# NODE_DW1000_A_V2.net
KiCad netlist of a schematic drawn in Altium Designer
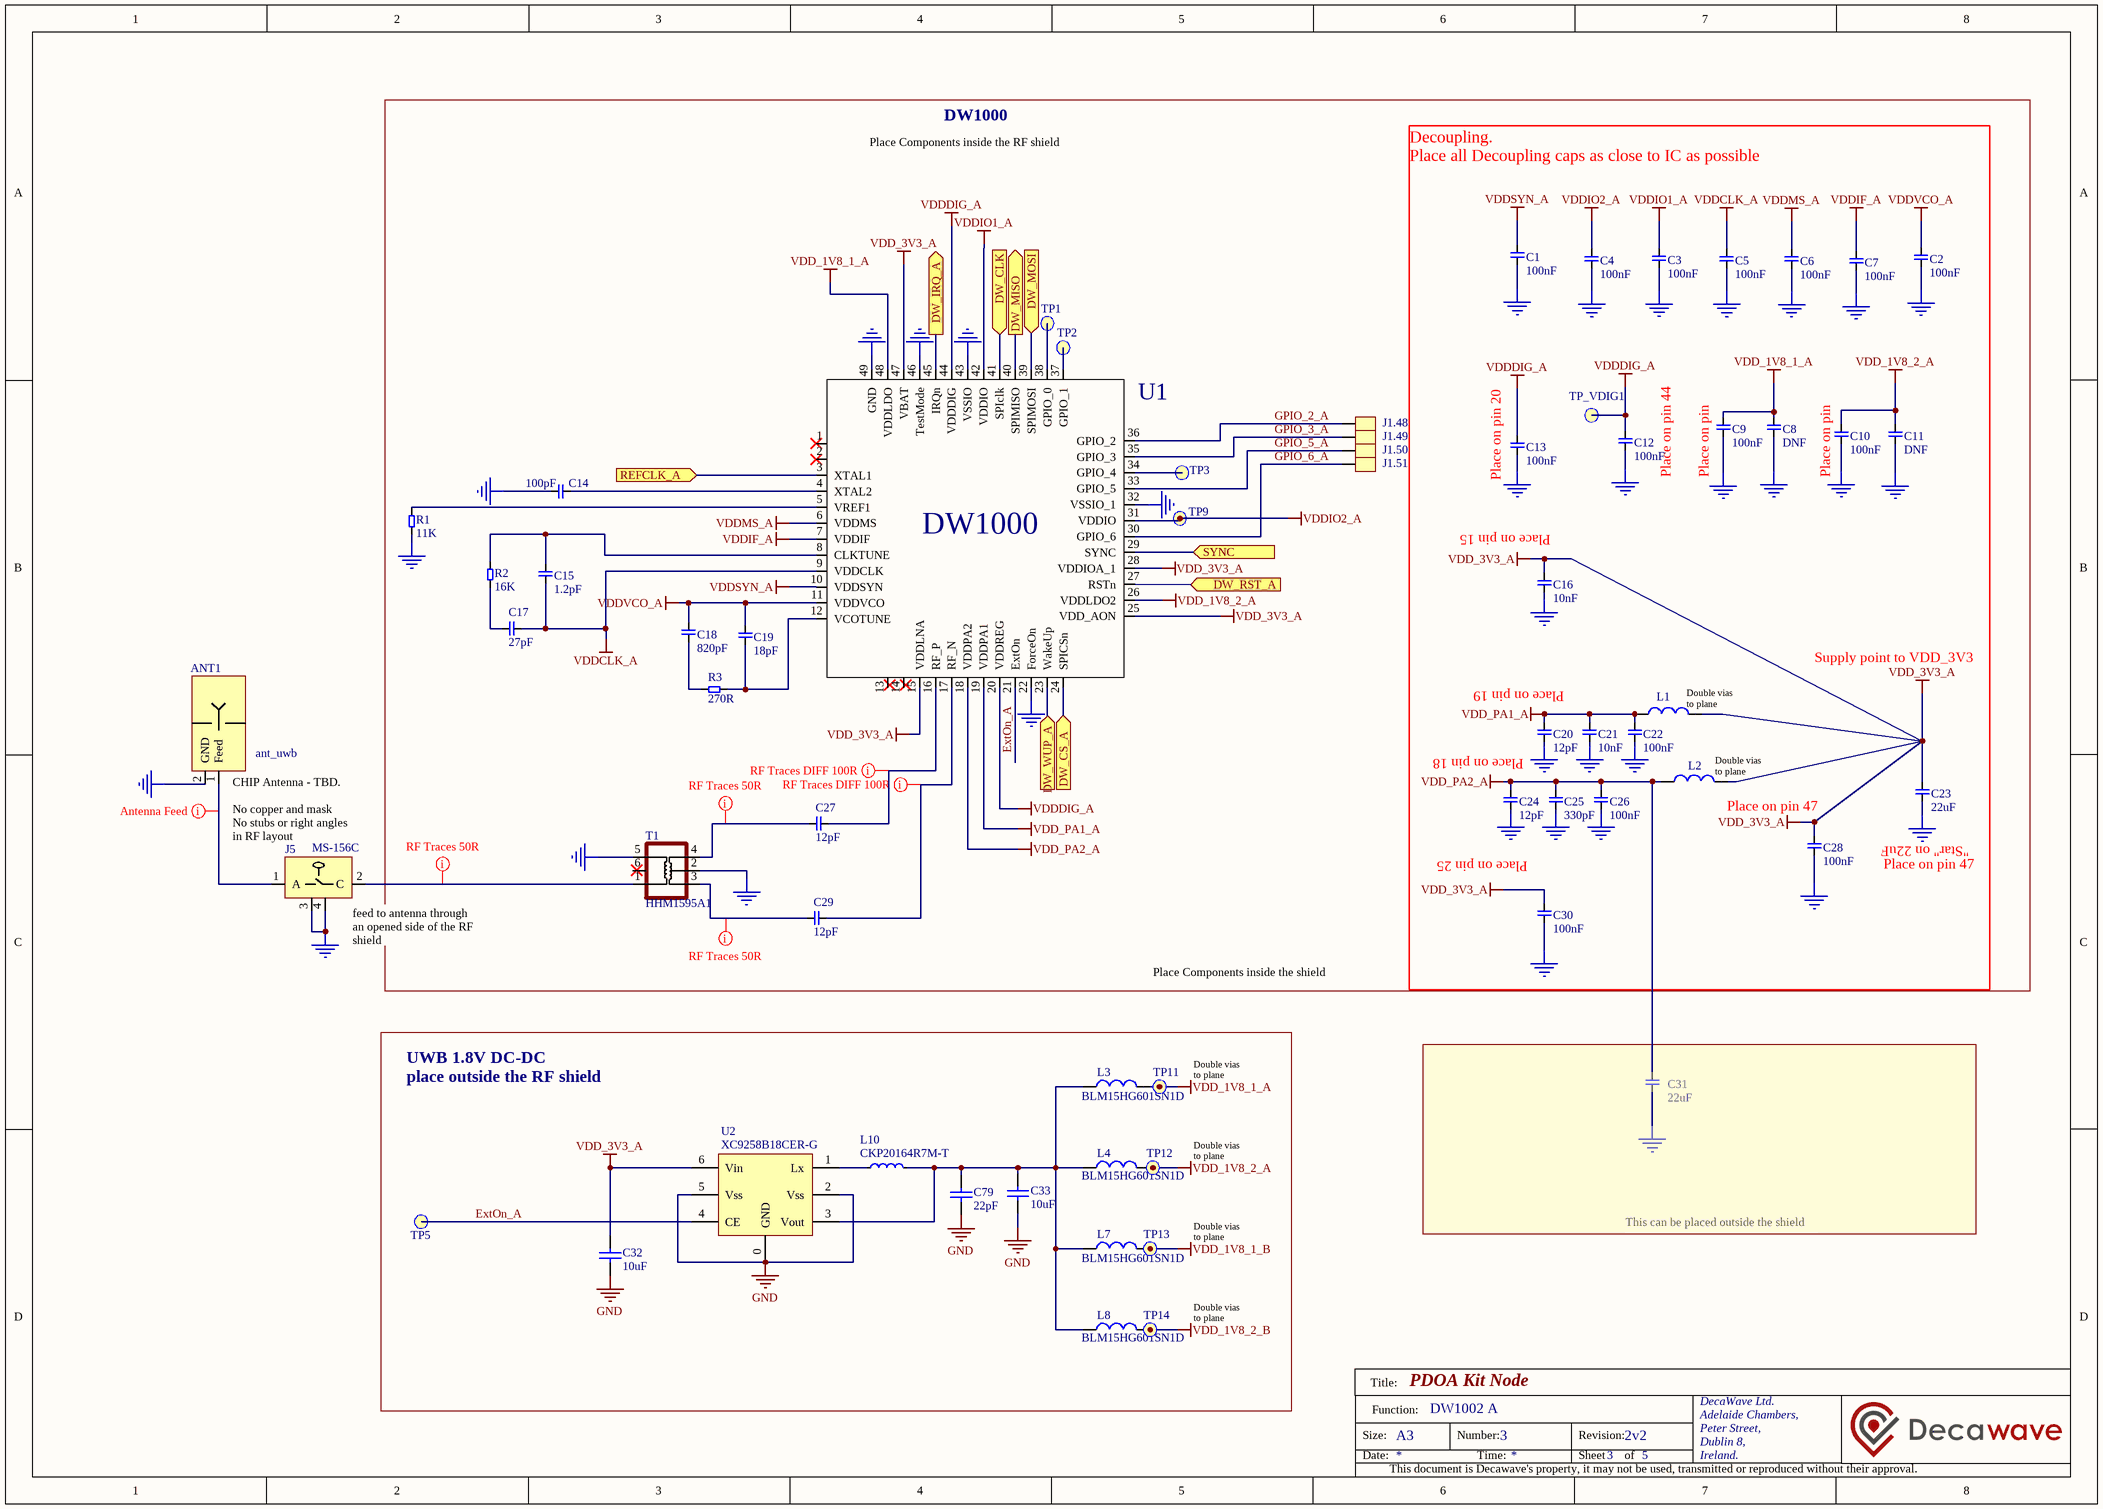
[diagram p0: NODE_DW1000_A_V2.SchDoc]

(export (version "E")
  (design (tool "Eeschema 10.0.6"))
  (components
    (comp (ref "ANT1")
      (value "ant_uwb")
      (footprint "ANT")
      (description "CHIP ANT")
      (libsource (lib "DecaWavedB") (part "ant_pcb"))
    )
    (comp (ref "C1")
      (value "100nF")
      (footprint "C0201-C")
      (description "100nF_0201_10%")
      (fields
        (field (name "MANUFACTURER") "Murata Electronics North America")
        (field (name "MANUFACTURER PART NUMBER") "GRM033C81E104KE14D")
      )
      (libsource (lib "DecaWavedB") (part "Capacitor - non polarized"))
    )
    (comp (ref "C2")
      (value "100nF")
      (footprint "C0201-C")
      (description "100nF_0201_10%")
      (fields
        (field (name "MANUFACTURER") "Murata Electronics North America")
        (field (name "MANUFACTURER PART NUMBER") "GRM033C81E104KE14D")
      )
      (libsource (lib "DecaWavedB") (part "Capacitor - non polarized"))
    )
    (comp (ref "C3")
      (value "100nF")
      (footprint "C0201-C")
      (description "100nF_0201_10%")
      (fields
        (field (name "MANUFACTURER") "Murata Electronics North America")
        (field (name "MANUFACTURER PART NUMBER") "GRM033C81E104KE14D")
      )
      (libsource (lib "DecaWavedB") (part "Capacitor - non polarized"))
    )
    (comp (ref "C4")
      (value "100nF")
      (footprint "C0201-C")
      (description "100nF_0201_10%")
      (fields
        (field (name "MANUFACTURER") "Murata Electronics North America")
        (field (name "MANUFACTURER PART NUMBER") "GRM033C81E104KE14D")
      )
      (libsource (lib "DecaWavedB") (part "Capacitor - non polarized"))
    )
    (comp (ref "C5")
      (value "100nF")
      (footprint "C0201-C")
      (description "100nF_0201_10%")
      (fields
        (field (name "MANUFACTURER") "Murata Electronics North America")
        (field (name "MANUFACTURER PART NUMBER") "GRM033C81E104KE14D")
      )
      (libsource (lib "DecaWavedB") (part "Capacitor - non polarized"))
    )
    (comp (ref "C6")
      (value "100nF")
      (footprint "C0201-C")
      (description "100nF_0201_10%")
      (fields
        (field (name "MANUFACTURER") "Murata Electronics North America")
        (field (name "MANUFACTURER PART NUMBER") "GRM033C81E104KE14D")
      )
      (libsource (lib "DecaWavedB") (part "Capacitor - non polarized"))
    )
    (comp (ref "C7")
      (value "100nF")
      (footprint "C0201-C")
      (description "100nF_0201_10%")
      (fields
        (field (name "MANUFACTURER") "Murata Electronics North America")
        (field (name "MANUFACTURER PART NUMBER") "GRM033C81E104KE14D")
      )
      (libsource (lib "DecaWavedB") (part "Capacitor - non polarized"))
    )
    (comp (ref "C8")
      (value "DNF")
      (footprint "C0402")
      (description "4.7uF_0402_10%")
      (fields
        (field (name "MANUFACTURER") "TDK")
        (field (name "MANUFACTURER PART NUMBER") "C1005X5R0J475K050BC")
      )
      (libsource (lib "DecaWavedB") (part "Capacitor - non polarized"))
    )
    (comp (ref "C9")
      (value "100nF")
      (footprint "C0201-C")
      (description "100nF_0201_10%")
      (fields
        (field (name "MANUFACTURER") "Murata Electronics North America")
        (field (name "MANUFACTURER PART NUMBER") "GRM033C81E104KE14D")
      )
      (libsource (lib "DecaWavedB") (part "Capacitor - non polarized"))
    )
    (comp (ref "C10")
      (value "100nF")
      (footprint "C0201-C")
      (description "100nF_0201_10%")
      (fields
        (field (name "MANUFACTURER") "Murata Electronics North America")
        (field (name "MANUFACTURER PART NUMBER") "GRM033C81E104KE14D")
      )
      (libsource (lib "DecaWavedB") (part "Capacitor - non polarized"))
    )
    (comp (ref "C11")
      (value "DNF")
      (footprint "C0402")
      (description "4.7uF_0402_10%")
      (fields
        (field (name "MANUFACTURER") "TDK")
        (field (name "MANUFACTURER PART NUMBER") "C1005X5R0J475K050BC")
      )
      (libsource (lib "DecaWavedB") (part "Capacitor - non polarized"))
    )
    (comp (ref "C12")
      (value "100nF")
      (footprint "C0201-C")
      (description "100nF_0201_10%")
      (fields
        (field (name "MANUFACTURER") "Murata Electronics North America")
        (field (name "MANUFACTURER PART NUMBER") "GRM033C81E104KE14D")
      )
      (libsource (lib "DecaWavedB") (part "Capacitor - non polarized"))
    )
    (comp (ref "C13")
      (value "100nF")
      (footprint "C0201-C")
      (description "100nF_0201_10%")
      (fields
        (field (name "MANUFACTURER") "Murata Electronics North America")
        (field (name "MANUFACTURER PART NUMBER") "GRM033C81E104KE14D")
      )
      (libsource (lib "DecaWavedB") (part "Capacitor - non polarized"))
    )
    (comp (ref "C14")
      (value "100pF")
      (footprint "C0402")
      (description "100pF_0402_10%")
      (fields
        (field (name "MANUFACTURER PART NUMBER") "GRM1555C1H101JA01D")
        (field (name "MANUFACTURER") "Murata Electronics North America")
      )
      (libsource (lib "DecaWavedB") (part "Capacitor - non polarized"))
    )
    (comp (ref "C15")
      (value "1.2pF")
      (footprint "C0201-C")
      (description "1.2pF_0201_10%")
      (fields
        (field (name "MANUFACTURER") "Murata Electronics North America")
        (field (name "MANUFACTURER PART NUMBER") "GRM0335C1E1R2CA01D")
      )
      (libsource (lib "DecaWavedB") (part "Capacitor - non polarized"))
    )
    (comp (ref "C16")
      (value "10nF")
      (footprint "C0201-C")
      (description "10nF_0201_10%")
      (fields
        (field (name "MANUFACTURER") "Murata Electronics North America")
        (field (name "MANUFACTURER PART NUMBER") "GRM033R61E103KA12D")
      )
      (libsource (lib "DecaWavedB") (part "Capacitor - non polarized"))
    )
    (comp (ref "C17")
      (value "27pF")
      (footprint "C0201-C")
      (description "27pF_0201_2%")
      (fields
        (field (name "MANUFACTURER") "Murata Electronics North America")
        (field (name "MANUFACTURER PART NUMBER") "GRM0335C1E270JA01D")
      )
      (libsource (lib "DecaWavedB") (part "Capacitor - non polarized"))
    )
    (comp (ref "C18")
      (value "820pF")
      (footprint "C0402")
      (description "820pF_0201_2%")
      (fields
        (field (name "MANUFACTURER") "Murata Electronics North America")
        (field (name "MANUFACTURER PART NUMBER") "GRM033R71E821KA01D")
      )
      (libsource (lib "DecaWavedB") (part "Capacitor - non polarized"))
    )
    (comp (ref "C19")
      (value "18pF")
      (footprint "C0201-C")
      (description "18pF_0201_1%")
      (fields
        (field (name "MANUFACTURER") "Murata Electronics North America")
        (field (name "MANUFACTURER PART NUMBER") "GRM0335C1H180JA01D")
      )
      (libsource (lib "DecaWavedB") (part "Capacitor - non polarized"))
    )
    (comp (ref "C20")
      (value "12pF")
      (footprint "C0201-C")
      (description "12pF_0201_1%")
      (fields
        (field (name "MANUFACTURER") "Murata Electronics North America")
        (field (name "MANUFACTURER PART NUMBER") "GRM0335C1E120JA01D")
      )
      (libsource (lib "DecaWavedB") (part "Capacitor - non polarized"))
    )
    (comp (ref "C21")
      (value "10nF")
      (footprint "C0201-C")
      (description "10nF_0201_10%")
      (fields
        (field (name "MANUFACTURER") "Murata Electronics North America")
        (field (name "MANUFACTURER PART NUMBER") "GRM033R61E103KA12D")
      )
      (libsource (lib "DecaWavedB") (part "Capacitor - non polarized"))
    )
    (comp (ref "C22")
      (value "100nF")
      (footprint "C0201-C")
      (description "100nF_0201_10%")
      (fields
        (field (name "MANUFACTURER") "Murata Electronics North America")
        (field (name "MANUFACTURER PART NUMBER") "GRM033C81E104KE14D")
      )
      (libsource (lib "DecaWavedB") (part "Capacitor - non polarized"))
    )
    (comp (ref "C23")
      (value "22uF")
      (footprint "C0603")
      (description "22uF_0603_10%")
      (fields
        (field (name "MANUFACTURER") "Murata Electronics North America")
        (field (name "MANUFACTURER PART NUMBER") "GRM188R60J226MEA0D")
      )
      (libsource (lib "DecaWavedB") (part "Capacitor - non polarized"))
    )
    (comp (ref "C24")
      (value "12pF")
      (footprint "C0201-C")
      (description "12pF_0201_1%")
      (fields
        (field (name "MANUFACTURER") "Murata Electronics North America")
        (field (name "MANUFACTURER PART NUMBER") "GRM0335C1E120JA01D")
      )
      (libsource (lib "DecaWavedB") (part "Capacitor - non polarized"))
    )
    (comp (ref "C25")
      (value "330pF")
      (footprint "C0201-C")
      (description "330pF_0201_10%")
      (fields
        (field (name "MANUFACTURER") "SamSung")
        (field (name "MANUFACTURER PART NUMBER") "CL03B331KA3NNNC")
      )
      (libsource (lib "DecaWavedB") (part "Capacitor - non polarized"))
    )
    (comp (ref "C26")
      (value "100nF")
      (footprint "C0201-C")
      (description "100nF_0201_10%")
      (fields
        (field (name "MANUFACTURER") "Murata Electronics North America")
        (field (name "MANUFACTURER PART NUMBER") "GRM033C81E104KE14D")
      )
      (libsource (lib "DecaWavedB") (part "Capacitor - non polarized"))
    )
    (comp (ref "C27")
      (value "12pF")
      (footprint "C0201-C")
      (description "12pF_0201_1%")
      (fields
        (field (name "MANUFACTURER") "Murata Electronics North America")
        (field (name "MANUFACTURER PART NUMBER") "GRM0335C1E120JA01D")
      )
      (libsource (lib "DecaWavedB") (part "Capacitor - non polarized"))
    )
    (comp (ref "C28")
      (value "100nF")
      (footprint "C0201-C")
      (description "100nF_0201_10%")
      (fields
        (field (name "MANUFACTURER") "Murata Electronics North America")
        (field (name "MANUFACTURER PART NUMBER") "GRM033C81E104KE14D")
      )
      (libsource (lib "DecaWavedB") (part "Capacitor - non polarized"))
    )
    (comp (ref "C29")
      (value "12pF")
      (footprint "C0201-C")
      (description "12pF_0201_1%")
      (fields
        (field (name "MANUFACTURER") "Murata Electronics North America")
        (field (name "MANUFACTURER PART NUMBER") "GRM0335C1E120JA01D")
      )
      (libsource (lib "DecaWavedB") (part "Capacitor - non polarized"))
    )
    (comp (ref "C30")
      (value "100nF")
      (footprint "C0201-C")
      (description "100nF_0201_10%")
      (fields
        (field (name "MANUFACTURER") "Murata Electronics North America")
        (field (name "MANUFACTURER PART NUMBER") "GRM033C81E104KE14D")
      )
      (libsource (lib "DecaWavedB") (part "Capacitor - non polarized"))
    )
    (comp (ref "C31")
      (value "22uF")
      (footprint "C0603")
      (description "22uF_0603_10%")
      (fields
        (field (name "MANUFACTURER") "Murata Electronics North America")
        (field (name "MANUFACTURER PART NUMBER") "GRM188R60J226MEA0D")
      )
      (libsource (lib "DecaWavedB") (part "Capacitor - non polarized"))
    )
    (comp (ref "C32")
      (value "10uF")
      (footprint "C0603")
      (description "CAP CER 10UF 6.3V X5R 0603")
      (fields
        (field (name "MANUFACTURER") "Murata Electronics North America")
        (field (name "MANUFACTURER PART NUMBER") "GRM188R60J106ME47D")
      )
      (libsource (lib "drak_Library") (part "GRM188R60J106ME84D"))
    )
    (comp (ref "C33")
      (value "10uF")
      (footprint "C0603")
      (description "CAP CER 10UF 6.3V X5R 0603")
      (fields
        (field (name "MANUFACTURER") "Murata Electronics North America")
        (field (name "MANUFACTURER PART NUMBER") "GRM188R60J106ME47D")
      )
      (libsource (lib "drak_Library") (part "GRM188R60J106ME84D"))
    )
    (comp (ref "C79")
      (value "22pF")
      (footprint "C0201")
      (description "CAP CER 10PF 25V NP0 0201")
      (fields
        (field (name "MANUFACTURER") "Murata Electronics North America")
        (field (name "MANUFACTURER PART NUMBER") "GRM0335C1E220JA01D")
      )
      (libsource (lib "Schlib1") (part "GRM0335C1E100JA01D"))
    )
    (comp (ref "J1.48")
      (value "EDGE_PIN")
      (footprint "PCB_EDGE_1MM")
      (description "PCB Edge pin")
      (libsource (lib "drak_Library") (part "PCB_EDGE_1MM"))
    )
    (comp (ref "J1.49")
      (value "EDGE_PIN")
      (footprint "PCB_EDGE_1MM")
      (description "PCB Edge pin")
      (libsource (lib "drak_Library") (part "PCB_EDGE_1MM"))
    )
    (comp (ref "J1.50")
      (value "EDGE_PIN")
      (footprint "PCB_EDGE_1MM")
      (description "PCB Edge pin")
      (libsource (lib "drak_Library") (part "PCB_EDGE_1MM"))
    )
    (comp (ref "J1.51")
      (value "EDGE_PIN")
      (footprint "PCB_EDGE_1MM")
      (description "PCB Edge pin")
      (libsource (lib "drak_Library") (part "PCB_EDGE_1MM"))
    )
    (comp (ref "J5")
      (value "coswitch")
      (footprint "RF_SWITCH_2P3X2P3")
      (description "COAX JACK STR 50 OHM SMD")
      (fields (field (name "MANUFACTURER PART NUMBER") "MS-156C") (field (name "MANUFACTURER") "Hirose"))
      (libsource (lib "DecaWavedB") (part "coswitch"))
    )
    (comp (ref "L1")
      (value "BLM15HG601SN1D")
      (footprint "L0402")
      (description "FERRITE BEAD, 0.7OHM, 300MA, 0402")
      (fields (field (name "MANUFACTURER") "Murata Electronics North America"))
      (libsource (lib "DecaWavedB") (part "inductor"))
    )
    (comp (ref "L2")
      (value "BLM15HG601SN1D")
      (footprint "L0402")
      (description "FERRITE BEAD, 0.7OHM, 300MA, 0402")
      (fields (field (name "MANUFACTURER") "Murata Electronics North America"))
      (libsource (lib "DecaWavedB") (part "inductor"))
    )
    (comp (ref "L3")
      (value "BLM15HG601SN1D")
      (footprint "L0402")
      (description "FERRITE BEAD, 0.7OHM, 300MA, 0402")
      (fields (field (name "MANUFACTURER") "Murata Electronics North America"))
      (libsource (lib "DecaWavedB") (part "inductor"))
    )
    (comp (ref "L4")
      (value "BLM15HG601SN1D")
      (footprint "L0402")
      (description "FERRITE BEAD, 0.7OHM, 300MA, 0402")
      (fields (field (name "MANUFACTURER") "Murata Electronics North America"))
      (libsource (lib "DecaWavedB") (part "inductor"))
    )
    (comp (ref "L7")
      (value "BLM15HG601SN1D")
      (footprint "L0402")
      (description "FERRITE BEAD, 0.7OHM, 300MA, 0402")
      (fields (field (name "MANUFACTURER") "Murata Electronics North America"))
      (libsource (lib "DecaWavedB") (part "inductor"))
    )
    (comp (ref "L8")
      (value "BLM15HG601SN1D")
      (footprint "L0402")
      (description "FERRITE BEAD, 0.7OHM, 300MA, 0402")
      (fields (field (name "MANUFACTURER") "Murata Electronics North America"))
      (libsource (lib "DecaWavedB") (part "inductor"))
    )
    (comp (ref "L10")
      (value "CKP20164R7M-T")
      (footprint "INDC2016X10N")
      (description "FIXED IND 2.2UH 1.2A 110 MOHM")
      (fields
        (field (name "MANUFACTURER") "Taiyo Yuden")
        (field (name "MANUFACTURER PART NUMBER") "CKP20162R2M-T")
      )
      (libsource (lib "Schlib1") (part "CKP20162R2M-T"))
    )
    (comp (ref "R1")
      (value "11K")
      (footprint "R0201-C")
      (description "11K_0201_1%")
      (fields
        (field (name "MANUFACTURER") "Yageo")
        (field (name "MANUFACTURER PART NUMBER") "RC0201FR-0711KL")
      )
      (libsource (lib "DecaWavedB") (part "Resistor"))
    )
    (comp (ref "R2")
      (value "16K")
      (footprint "R0201-C")
      (description "16K_0201_1%")
      (fields
        (field (name "MANUFACTURER") "Yageo")
        (field (name "MANUFACTURER PART NUMBER") "RC0201FR-0716KL")
      )
      (libsource (lib "DecaWavedB") (part "Resistor"))
    )
    (comp (ref "R3")
      (value "270R")
      (footprint "R0201-C")
      (description "270R_0201_1%")
      (fields
        (field (name "MANUFACTURER") "Yageo")
        (field (name "MANUFACTURER PART NUMBER") "RC0201FR-07270RL")
      )
      (libsource (lib "DecaWavedB") (part "Resistor"))
    )
    (comp (ref "T1")
      (value "HHM1595A1")
      (footprint "TRANS4_0P65_2P15X1P4")
      (description "SMT UWB Balun 3-8Ghz")
      (fields (field (name "MANUFACTURER") "TDK"))
      (libsource (lib "DecaWavedB") (part "HHM1595A1"))
    )
    (comp (ref "TP1")
      (value "TP")
      (footprint "TP_40S")
      (description "test point")
      (libsource (lib "AoAB") (part "TP"))
    )
    (comp (ref "TP2")
      (value "TP")
      (footprint "TP_40S")
      (description "test point")
      (libsource (lib "AoAB") (part "TP"))
    )
    (comp (ref "TP3")
      (value "TP")
      (footprint "TP_40S")
      (description "test point")
      (libsource (lib "AoAB") (part "TP"))
    )
    (comp (ref "TP5")
      (value "TP")
      (footprint "TP_40S")
      (description "test point")
      (libsource (lib "AoAB") (part "TP"))
    )
    (comp (ref "TP9")
      (value "TP")
      (footprint "TP_40S")
      (description "test point")
      (libsource (lib "AoAB") (part "TP"))
    )
    (comp (ref "TP11")
      (value "TP")
      (footprint "TP_40S")
      (description "test point")
      (libsource (lib "AoAB") (part "TP"))
    )
    (comp (ref "TP12")
      (value "TP")
      (footprint "TP_40S")
      (description "test point")
      (libsource (lib "AoAB") (part "TP"))
    )
    (comp (ref "TP13")
      (value "TP")
      (footprint "TP_40S")
      (description "test point")
      (libsource (lib "AoAB") (part "TP"))
    )
    (comp (ref "TP14")
      (value "TP")
      (footprint "TP_40S")
      (description "test point")
      (libsource (lib "AoAB") (part "TP"))
    )
    (comp (ref "TP_VDIG1")
      (value "TP")
      (footprint "TP_40S")
      (description "test point")
      (libsource (lib "AoAB") (part "TP"))
    )
    (comp (ref "U1")
      (value "DW1000 IC")
      (footprint "QFN48_0P4_6P0X6P0_T")
      (description "UMB Transceiver")
      (fields (field (name "MANUFACTURER PART NUMBER") "DW1000") (field (name "MANUFACTURER") "Decawave"))
      (libsource (lib "DecaWavedB") (part "DW1000_QFN_48"))
    )
    (comp (ref "U2")
      (value "XC9258B18CER-G")
      (footprint "USP-6C")
      (fields (field (name "MANUFACTURER") "Torex"))
      (libsource (lib "LGA12_LGA14_LIB") (part "XC9257/8"))
    )
  )
  (nets
    (net (code "1") (name "/DW_CLK") (class "Default")
      (node (ref "U1") (pin "41") (pinfunction "SPIclk_41") (pintype "passive"))
    )
    (net (code "2") (name "/DW_CS_A") (class "Default")
      (node (ref "U1") (pin "24") (pinfunction "SPICSn_24") (pintype "passive"))
    )
    (net (code "3") (name "/DW_IRQ_A") (class "Default")
      (node (ref "U1") (pin "45") (pinfunction "IRQn_45") (pintype "passive"))
    )
    (net (code "4") (name "/DW_MISO") (class "Default")
      (node (ref "U1") (pin "40") (pinfunction "SPIMISO_40") (pintype "passive"))
    )
    (net (code "5") (name "/DW_MOSI") (class "Default")
      (node (ref "U1") (pin "39") (pinfunction "SPIMOSI_39") (pintype "passive"))
    )
    (net (code "6") (name "/DW_RST_A") (class "Default")
      (node (ref "U1") (pin "27") (pinfunction "RSTn_27") (pintype "passive"))
    )
    (net (code "7") (name "/DW_WUP_A") (class "Default")
      (node (ref "U1") (pin "23") (pinfunction "WakeUp_23") (pintype "passive"))
    )
    (net (code "8") (name "/ExtOn_A") (class "Default")
      (node (ref "TP5") (pin "1") (pinfunction "1_1") (pintype "passive"))
      (node (ref "U1") (pin "21") (pinfunction "ExtOn_21") (pintype "passive"))
      (node (ref "U2") (pin "4") (pinfunction "CE_4") (pintype "passive"))
    )
    (net (code "9") (name "/GPIO_2_A") (class "Default")
      (node (ref "J1.48") (pin "0") (pinfunction "0_0") (pintype "passive"))
      (node (ref "U1") (pin "36") (pinfunction "GPIO_2_36") (pintype "passive"))
    )
    (net (code "10") (name "/GPIO_3_A") (class "Default")
      (node (ref "J1.49") (pin "0") (pinfunction "0_0") (pintype "passive"))
      (node (ref "U1") (pin "35") (pinfunction "GPIO_3_35") (pintype "passive"))
    )
    (net (code "11") (name "/GPIO_5_A") (class "Default")
      (node (ref "J1.50") (pin "0") (pinfunction "0_0") (pintype "passive"))
      (node (ref "U1") (pin "33") (pinfunction "GPIO_5_33") (pintype "passive"))
    )
    (net (code "12") (name "/GPIO_6_A") (class "Default")
      (node (ref "J1.51") (pin "0") (pinfunction "0_0") (pintype "passive"))
      (node (ref "U1") (pin "30") (pinfunction "GPIO_6_30") (pintype "passive"))
    )
    (net (code "13") (name "/REFCLK_A") (class "Default")
      (node (ref "U1") (pin "3") (pinfunction "XTAL1_3") (pintype "passive"))
    )
    (net (code "14") (name "/SYNC") (class "Default")
      (node (ref "U1") (pin "29") (pinfunction "SYNC_29") (pintype "passive"))
    )
    (net (code "15") (name "GND") (class "Default")
      (node (ref "ANT1") (pin "2") (pinfunction "GND_2") (pintype "passive"))
      (node (ref "C1") (pin "1") (pinfunction "1_1") (pintype "passive"))
      (node (ref "C10") (pin "1") (pinfunction "1_1") (pintype "passive"))
      (node (ref "C11") (pin "1") (pinfunction "1_1") (pintype "passive"))
      (node (ref "C12") (pin "1") (pinfunction "1_1") (pintype "passive"))
      (node (ref "C13") (pin "1") (pinfunction "1_1") (pintype "passive"))
      (node (ref "C14") (pin "2") (pinfunction "2_2") (pintype "passive"))
      (node (ref "C16") (pin "1") (pinfunction "1_1") (pintype "passive"))
      (node (ref "C2") (pin "1") (pinfunction "1_1") (pintype "passive"))
      (node (ref "C20") (pin "1") (pinfunction "1_1") (pintype "passive"))
      (node (ref "C21") (pin "1") (pinfunction "1_1") (pintype "passive"))
      (node (ref "C22") (pin "1") (pinfunction "1_1") (pintype "passive"))
      (node (ref "C23") (pin "1") (pinfunction "1_1") (pintype "passive"))
      (node (ref "C24") (pin "1") (pinfunction "1_1") (pintype "passive"))
      (node (ref "C25") (pin "1") (pinfunction "1_1") (pintype "passive"))
      (node (ref "C26") (pin "1") (pinfunction "1_1") (pintype "passive"))
      (node (ref "C28") (pin "1") (pinfunction "1_1") (pintype "passive"))
      (node (ref "C3") (pin "1") (pinfunction "1_1") (pintype "passive"))
      (node (ref "C30") (pin "1") (pinfunction "1_1") (pintype "passive"))
      (node (ref "C31") (pin "1") (pinfunction "1_1") (pintype "passive"))
      (node (ref "C32") (pin "1") (pinfunction "1_1") (pintype "passive"))
      (node (ref "C33") (pin "1") (pinfunction "1_1") (pintype "passive"))
      (node (ref "C4") (pin "1") (pinfunction "1_1") (pintype "passive"))
      (node (ref "C5") (pin "1") (pinfunction "1_1") (pintype "passive"))
      (node (ref "C6") (pin "1") (pinfunction "1_1") (pintype "passive"))
      (node (ref "C7") (pin "1") (pinfunction "1_1") (pintype "passive"))
      (node (ref "C79") (pin "1") (pinfunction "1_1") (pintype "passive"))
      (node (ref "C8") (pin "1") (pinfunction "1_1") (pintype "passive"))
      (node (ref "C9") (pin "1") (pinfunction "1_1") (pintype "passive"))
      (node (ref "J5") (pin "3") (pinfunction "GND_3") (pintype "passive"))
      (node (ref "J5") (pin "4") (pinfunction "GND_4") (pintype "passive"))
      (node (ref "R1") (pin "1") (pinfunction "1_1") (pintype "passive"))
      (node (ref "T1") (pin "2") (pinfunction "2_2") (pintype "passive"))
      (node (ref "T1") (pin "5") (pinfunction "5_5") (pintype "passive"))
      (node (ref "U1") (pin "22") (pinfunction "ForceOn_22") (pintype "passive"))
      (node (ref "U1") (pin "32") (pinfunction "VSSIO_1_32") (pintype "passive"))
      (node (ref "U1") (pin "43") (pinfunction "VSSIO_43") (pintype "passive"))
      (node (ref "U1") (pin "46") (pinfunction "TestMode_46") (pintype "passive"))
      (node (ref "U1") (pin "49") (pinfunction "GND_49") (pintype "passive"))
      (node (ref "U2") (pin "0") (pinfunction "GND_0") (pintype "passive"))
      (node (ref "U2") (pin "2") (pinfunction "Vss_2") (pintype "passive"))
      (node (ref "U2") (pin "5") (pinfunction "Vss_5") (pintype "passive"))
    )
    (net (code "16") (name "Net-(ANT1-Feed)") (class "Default")
      (node (ref "ANT1") (pin "1") (pinfunction "Feed_1") (pintype "passive"))
      (node (ref "J5") (pin "1") (pinfunction "A_1") (pintype "passive"))
    )
    (net (code "17") (name "Net-(C17-Pad2)") (class "Default")
      (node (ref "C17") (pin "2") (pinfunction "2_2") (pintype "passive"))
      (node (ref "R2") (pin "1") (pinfunction "1_1") (pintype "passive"))
    )
    (net (code "18") (name "Net-(C18-Pad1)") (class "Default")
      (node (ref "C18") (pin "1") (pinfunction "1_1") (pintype "passive"))
      (node (ref "R3") (pin "2") (pinfunction "2_2") (pintype "passive"))
    )
    (net (code "19") (name "Net-(C27-Pad1)") (class "Default")
      (node (ref "C27") (pin "1") (pinfunction "1_1") (pintype "passive"))
      (node (ref "T1") (pin "4") (pinfunction "4_4") (pintype "passive"))
    )
    (net (code "20") (name "Net-(C29-Pad1)") (class "Default")
      (node (ref "C29") (pin "1") (pinfunction "1_1") (pintype "passive"))
      (node (ref "T1") (pin "3") (pinfunction "3_3") (pintype "passive"))
    )
    (net (code "21") (name "Net-(J5-C)") (class "Default")
      (node (ref "J5") (pin "2") (pinfunction "C_2") (pintype "passive"))
      (node (ref "T1") (pin "1") (pinfunction "1_1") (pintype "passive"))
    )
    (net (code "22") (name "Net-(U1-CLKTUNE)") (class "Default")
      (node (ref "C15") (pin "2") (pinfunction "2_2") (pintype "passive"))
      (node (ref "R2") (pin "2") (pinfunction "2_2") (pintype "passive"))
      (node (ref "U1") (pin "8") (pinfunction "CLKTUNE_8") (pintype "passive"))
    )
    (net (code "23") (name "Net-(U1-GPIO_0)") (class "Default")
      (node (ref "TP1") (pin "1") (pinfunction "1_1") (pintype "passive"))
      (node (ref "U1") (pin "38") (pinfunction "GPIO_0_38") (pintype "passive"))
    )
    (net (code "24") (name "Net-(U1-GPIO_1)") (class "Default")
      (node (ref "TP2") (pin "1") (pinfunction "1_1") (pintype "passive"))
      (node (ref "U1") (pin "37") (pinfunction "GPIO_1_37") (pintype "passive"))
    )
    (net (code "25") (name "Net-(U1-GPIO_4)") (class "Default")
      (node (ref "TP3") (pin "1") (pinfunction "1_1") (pintype "passive"))
      (node (ref "U1") (pin "34") (pinfunction "GPIO_4_34") (pintype "passive"))
    )
    (net (code "26") (name "Net-(U1-RF_N)") (class "Default")
      (node (ref "C29") (pin "2") (pinfunction "2_2") (pintype "passive"))
      (node (ref "U1") (pin "17") (pinfunction "RF_N_17") (pintype "passive"))
    )
    (net (code "27") (name "Net-(U1-RF_P)") (class "Default")
      (node (ref "C27") (pin "2") (pinfunction "2_2") (pintype "passive"))
      (node (ref "U1") (pin "16") (pinfunction "RF_P_16") (pintype "passive"))
    )
    (net (code "28") (name "Net-(U1-VCOTUNE)") (class "Default")
      (node (ref "C19") (pin "2") (pinfunction "2_2") (pintype "passive"))
      (node (ref "R3") (pin "1") (pinfunction "1_1") (pintype "passive"))
      (node (ref "U1") (pin "12") (pinfunction "VCOTUNE_12") (pintype "passive"))
    )
    (net (code "29") (name "Net-(U1-VREF1)") (class "Default")
      (node (ref "R1") (pin "2") (pinfunction "2_2") (pintype "passive"))
      (node (ref "U1") (pin "5") (pinfunction "VREF1_5") (pintype "passive"))
    )
    (net (code "30") (name "Net-(U1-XTAL2)") (class "Default")
      (node (ref "C14") (pin "1") (pinfunction "1_1") (pintype "passive"))
      (node (ref "U1") (pin "4") (pinfunction "XTAL2_4") (pintype "passive"))
    )
    (net (code "31") (name "Net-(U2-Lx)") (class "Default")
      (node (ref "L10") (pin "1") (pinfunction "1_1") (pintype "passive"))
      (node (ref "U2") (pin "1") (pinfunction "Lx_1") (pintype "passive"))
    )
    (net (code "32") (name "Net-(U2-Vout)") (class "Default")
      (node (ref "C33") (pin "2") (pinfunction "2_2") (pintype "passive"))
      (node (ref "C79") (pin "2") (pinfunction "2_2") (pintype "passive"))
      (node (ref "L10") (pin "2") (pinfunction "2_2") (pintype "passive"))
      (node (ref "L3") (pin "1") (pinfunction "1_1") (pintype "passive"))
      (node (ref "L4") (pin "1") (pinfunction "1_1") (pintype "passive"))
      (node (ref "L7") (pin "1") (pinfunction "1_1") (pintype "passive"))
      (node (ref "L8") (pin "1") (pinfunction "1_1") (pintype "passive"))
      (node (ref "U2") (pin "3") (pinfunction "Vout_3") (pintype "passive"))
    )
    (net (code "33") (name "VDDCLK_A") (class "Default")
      (node (ref "C15") (pin "1") (pinfunction "1_1") (pintype "passive"))
      (node (ref "C17") (pin "1") (pinfunction "1_1") (pintype "passive"))
      (node (ref "C5") (pin "2") (pinfunction "2_2") (pintype "passive"))
      (node (ref "U1") (pin "9") (pinfunction "VDDCLK_9") (pintype "passive"))
    )
    (net (code "34") (name "VDDDIG_A") (class "Default")
      (node (ref "C12") (pin "2") (pinfunction "2_2") (pintype "passive"))
      (node (ref "C13") (pin "2") (pinfunction "2_2") (pintype "passive"))
      (node (ref "TP_VDIG1") (pin "1") (pinfunction "1_1") (pintype "passive"))
      (node (ref "U1") (pin "20") (pinfunction "VDDREG_20") (pintype "passive"))
      (node (ref "U1") (pin "44") (pinfunction "VDDDIG_44") (pintype "passive"))
    )
    (net (code "35") (name "VDDIF_A") (class "Default")
      (node (ref "C7") (pin "2") (pinfunction "2_2") (pintype "passive"))
      (node (ref "U1") (pin "7") (pinfunction "VDDIF_7") (pintype "passive"))
    )
    (net (code "36") (name "VDDIO1_A") (class "Default")
      (node (ref "C3") (pin "2") (pinfunction "2_2") (pintype "passive"))
      (node (ref "U1") (pin "42") (pinfunction "VDDIO_42") (pintype "passive"))
    )
    (net (code "37") (name "VDDIO2_A") (class "Default")
      (node (ref "C4") (pin "2") (pinfunction "2_2") (pintype "passive"))
      (node (ref "TP9") (pin "1") (pinfunction "1_1") (pintype "passive"))
      (node (ref "U1") (pin "31") (pinfunction "VDDIO_31") (pintype "passive"))
    )
    (net (code "38") (name "VDDMS_A") (class "Default")
      (node (ref "C6") (pin "2") (pinfunction "2_2") (pintype "passive"))
      (node (ref "U1") (pin "6") (pinfunction "VDDMS_6") (pintype "passive"))
    )
    (net (code "39") (name "VDDSYN_A") (class "Default")
      (node (ref "C1") (pin "2") (pinfunction "2_2") (pintype "passive"))
      (node (ref "U1") (pin "10") (pinfunction "VDDSYN_10") (pintype "passive"))
    )
    (net (code "40") (name "VDDVCO_A") (class "Default")
      (node (ref "C18") (pin "2") (pinfunction "2_2") (pintype "passive"))
      (node (ref "C19") (pin "1") (pinfunction "1_1") (pintype "passive"))
      (node (ref "C2") (pin "2") (pinfunction "2_2") (pintype "passive"))
      (node (ref "U1") (pin "11") (pinfunction "VDDVCO_11") (pintype "passive"))
    )
    (net (code "41") (name "VDD_1V8_1_A") (class "Default")
      (node (ref "C8") (pin "2") (pinfunction "2_2") (pintype "passive"))
      (node (ref "C9") (pin "2") (pinfunction "2_2") (pintype "passive"))
      (node (ref "L3") (pin "2") (pinfunction "2_2") (pintype "passive"))
      (node (ref "TP11") (pin "1") (pinfunction "1_1") (pintype "passive"))
      (node (ref "U1") (pin "48") (pinfunction "VDDLDO_48") (pintype "passive"))
    )
    (net (code "42") (name "VDD_1V8_1_B") (class "Default")
      (node (ref "L7") (pin "2") (pinfunction "2_2") (pintype "passive"))
      (node (ref "TP13") (pin "1") (pinfunction "1_1") (pintype "passive"))
    )
    (net (code "43") (name "VDD_1V8_2_A") (class "Default")
      (node (ref "C10") (pin "2") (pinfunction "2_2") (pintype "passive"))
      (node (ref "C11") (pin "2") (pinfunction "2_2") (pintype "passive"))
      (node (ref "L4") (pin "2") (pinfunction "2_2") (pintype "passive"))
      (node (ref "TP12") (pin "1") (pinfunction "1_1") (pintype "passive"))
      (node (ref "U1") (pin "26") (pinfunction "VDDLDO2_26") (pintype "passive"))
    )
    (net (code "44") (name "VDD_1V8_2_B") (class "Default")
      (node (ref "L8") (pin "2") (pinfunction "2_2") (pintype "passive"))
      (node (ref "TP14") (pin "1") (pinfunction "1_1") (pintype "passive"))
    )
    (net (code "45") (name "VDD_3V3_A") (class "Default")
      (node (ref "C16") (pin "2") (pinfunction "2_2") (pintype "passive"))
      (node (ref "C23") (pin "2") (pinfunction "2_2") (pintype "passive"))
      (node (ref "C28") (pin "2") (pinfunction "2_2") (pintype "passive"))
      (node (ref "C30") (pin "2") (pinfunction "2_2") (pintype "passive"))
      (node (ref "C32") (pin "2") (pinfunction "2_2") (pintype "passive"))
      (node (ref "L1") (pin "2") (pinfunction "2_2") (pintype "passive"))
      (node (ref "L2") (pin "2") (pinfunction "2_2") (pintype "passive"))
      (node (ref "U1") (pin "15") (pinfunction "VDDLNA_15") (pintype "passive"))
      (node (ref "U1") (pin "25") (pinfunction "VDD_AON_25") (pintype "passive"))
      (node (ref "U1") (pin "28") (pinfunction "VDDIOA_1_28") (pintype "passive"))
      (node (ref "U1") (pin "47") (pinfunction "VBAT_47") (pintype "passive"))
      (node (ref "U2") (pin "6") (pinfunction "Vin_6") (pintype "passive"))
    )
    (net (code "46") (name "VDD_PA1_A") (class "Default")
      (node (ref "C20") (pin "2") (pinfunction "2_2") (pintype "passive"))
      (node (ref "C21") (pin "2") (pinfunction "2_2") (pintype "passive"))
      (node (ref "C22") (pin "2") (pinfunction "2_2") (pintype "passive"))
      (node (ref "L1") (pin "1") (pinfunction "1_1") (pintype "passive"))
      (node (ref "U1") (pin "19") (pinfunction "VDDPA1_19") (pintype "passive"))
    )
    (net (code "47") (name "VDD_PA2_A") (class "Default")
      (node (ref "C24") (pin "2") (pinfunction "2_2") (pintype "passive"))
      (node (ref "C25") (pin "2") (pinfunction "2_2") (pintype "passive"))
      (node (ref "C26") (pin "2") (pinfunction "2_2") (pintype "passive"))
      (node (ref "C31") (pin "2") (pinfunction "2_2") (pintype "passive"))
      (node (ref "L2") (pin "1") (pinfunction "1_1") (pintype "passive"))
      (node (ref "U1") (pin "18") (pinfunction "VDDPA2_18") (pintype "passive"))
    )
    (net (code "48") (name "unconnected-(T1-Pad6)") (class "Default")
      (node (ref "T1") (pin "6") (pinfunction "6_6") (pintype "passive"))
    )
    (net (code "49") (name "unconnected-(U1-Pad1)") (class "Default")
      (node (ref "U1") (pin "1") (pintype "passive"))
    )
    (net (code "50") (name "unconnected-(U1-Pad2)") (class "Default")
      (node (ref "U1") (pin "2") (pintype "passive"))
    )
    (net (code "51") (name "unconnected-(U1-Pad13)") (class "Default")
      (node (ref "U1") (pin "13") (pintype "passive"))
    )
    (net (code "52") (name "unconnected-(U1-Pad14)") (class "Default")
      (node (ref "U1") (pin "14") (pintype "passive"))
    )
  )
)
